# PMIC_Debug.net
KiCad netlist of a schematic drawn in Altium Designer
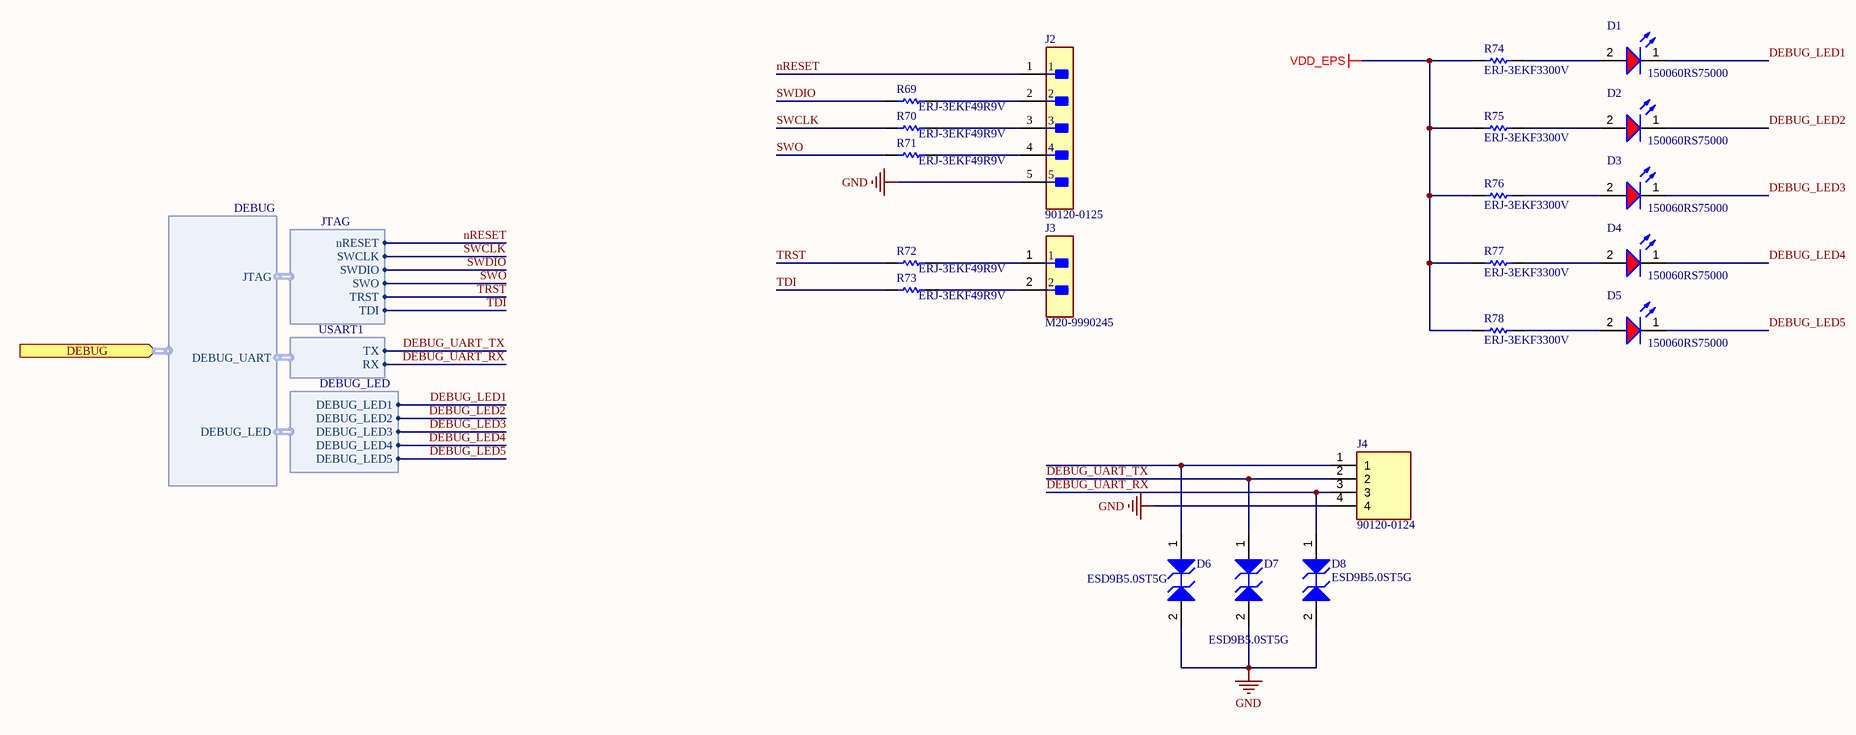
[diagram p0: PMIC_Debug.SchDoc]

(export (version "E")
  (design (tool "Eeschema 10.0.6"))
  (components
    (comp (ref "D1")
      (value "150060RS75000")
      (footprint "WL-SMCW_0603_150060xx75000")
      (description "LED Low-Power Uni-Color Red 630nm 2V 2-Pin Chip 0603(1608Metric) T/R")
      (libsource (lib "Altium Content Vault") (part "LED_Red_2A-1K"))
    )
    (comp (ref "D2")
      (value "150060RS75000")
      (footprint "WL-SMCW_0603_150060xx75000")
      (description "LED Low-Power Uni-Color Red 630nm 2V 2-Pin Chip 0603(1608Metric) T/R")
      (libsource (lib "Altium Content Vault") (part "LED_Red_2A-1K"))
    )
    (comp (ref "D3")
      (value "150060RS75000")
      (footprint "WL-SMCW_0603_150060xx75000")
      (description "LED Low-Power Uni-Color Red 630nm 2V 2-Pin Chip 0603(1608Metric) T/R")
      (libsource (lib "Altium Content Vault") (part "LED_Red_2A-1K"))
    )
    (comp (ref "D4")
      (value "150060RS75000")
      (footprint "WL-SMCW_0603_150060xx75000")
      (description "LED Low-Power Uni-Color Red 630nm 2V 2-Pin Chip 0603(1608Metric) T/R")
      (libsource (lib "Altium Content Vault") (part "LED_Red_2A-1K"))
    )
    (comp (ref "D5")
      (value "150060RS75000")
      (footprint "WL-SMCW_0603_150060xx75000")
      (description "LED Low-Power Uni-Color Red 630nm 2V 2-Pin Chip 0603(1608Metric) T/R")
      (libsource (lib "Altium Content Vault") (part "LED_Red_2A-1K"))
    )
    (comp (ref "D6")
      (value "ESD9B5.0ST5G")
      (footprint "ONSC-SOD-923-2-514AB-01_V")
      (fields (field (name "MANUFACTURER") "On Semiconductor"))
      (libsource (lib "Altium Content Vault") (part "ONSC-A1A2-2"))
    )
    (comp (ref "D7")
      (value "ESD9B5.0ST5G")
      (footprint "ONSC-SOD-923-2-514AB-01_V")
      (fields (field (name "MANUFACTURER") "On Semiconductor"))
      (libsource (lib "Altium Content Vault") (part "ONSC-A1A2-2"))
    )
    (comp (ref "D8")
      (value "ESD9B5.0ST5G")
      (footprint "ONSC-SOD-923-2-514AB-01_V")
      (fields (field (name "MANUFACTURER") "On Semiconductor"))
      (libsource (lib "Altium Content Vault") (part "ONSC-A1A2-2"))
    )
    (comp (ref "J2")
      (value "90120-0125")
      (footprint "FP-90120-0125-MFG")
      (description "90120-0125 2.54mm Pitch C-Grid III Header, Single Row, Vertical, 5 Circuits, Tin (Sn) Plating")
      (libsource (lib "Altium Content Vault") (part "bf93c07fd2649a848d0ec8585582aab"))
    )
    (comp (ref "J3")
      (value "M20-9990245")
      (footprint "FP-M20-9990245-MFG")
      (description "CONN HEADER VERT 2POS 2.54MM")
      (fields (field (name "VOLTAGE") "50V"))
      (libsource (lib "Altium Content Vault") (part "3bc925449376181038e59eaffc5286c"))
    )
    (comp (ref "J4")
      (value "90120-0124")
      (footprint "SamacSys:HDRV4W65P0X254_1X4_1016X254X945P")
      (description "Connector")
      (fields (field (name "MOUSER PART NUMBER") "538-90120-0124"))
      (libsource (lib "*") (part "90120-0124"))
    )
    (comp (ref "R69")
      (value "ERJ-3EKF49R9V")
      (footprint "RESC1608X55X30ML15T15")
      (fields (field (name "MANUFACTURER") "Panasonic"))
      (libsource (lib "Altium Content Vault") (part "RES"))
    )
    (comp (ref "R70")
      (value "ERJ-3EKF49R9V")
      (footprint "RESC1608X55X30ML15T15")
      (fields (field (name "MANUFACTURER") "Panasonic"))
      (libsource (lib "Altium Content Vault") (part "RES"))
    )
    (comp (ref "R71")
      (value "ERJ-3EKF49R9V")
      (footprint "RESC1608X55X30ML15T15")
      (fields (field (name "MANUFACTURER") "Panasonic"))
      (libsource (lib "Altium Content Vault") (part "RES"))
    )
    (comp (ref "R72")
      (value "ERJ-3EKF49R9V")
      (footprint "RESC1608X55X30ML15T15")
      (fields (field (name "MANUFACTURER") "Panasonic"))
      (libsource (lib "Altium Content Vault") (part "RES"))
    )
    (comp (ref "R73")
      (value "ERJ-3EKF49R9V")
      (footprint "RESC1608X55X30ML15T15")
      (fields (field (name "MANUFACTURER") "Panasonic"))
      (libsource (lib "Altium Content Vault") (part "RES"))
    )
    (comp (ref "R74")
      (value "ERJ-3EKF3300V")
      (footprint "RESC1608X55X30LL15T15")
      (description "Chip Resistor, 330 Ohm, +/- 1%, 0.1 W, -55 to 155 degC, 0603 (1608 Metric), RoHS, Tape and Reel")
      (libsource (lib "Altium Content Vault") (part "RES-2"))
    )
    (comp (ref "R75")
      (value "ERJ-3EKF3300V")
      (footprint "RESC1608X55X30LL15T15")
      (description "Chip Resistor, 330 Ohm, +/- 1%, 0.1 W, -55 to 155 degC, 0603 (1608 Metric), RoHS, Tape and Reel")
      (libsource (lib "Altium Content Vault") (part "RES-2"))
    )
    (comp (ref "R76")
      (value "ERJ-3EKF3300V")
      (footprint "RESC1608X55X30LL15T15")
      (description "Chip Resistor, 330 Ohm, +/- 1%, 0.1 W, -55 to 155 degC, 0603 (1608 Metric), RoHS, Tape and Reel")
      (libsource (lib "Altium Content Vault") (part "RES-2"))
    )
    (comp (ref "R77")
      (value "ERJ-3EKF3300V")
      (footprint "RESC1608X55X30LL15T15")
      (description "Chip Resistor, 330 Ohm, +/- 1%, 0.1 W, -55 to 155 degC, 0603 (1608 Metric), RoHS, Tape and Reel")
      (libsource (lib "Altium Content Vault") (part "RES-2"))
    )
    (comp (ref "R78")
      (value "ERJ-3EKF3300V")
      (footprint "RESC1608X55X30LL15T15")
      (description "Chip Resistor, 330 Ohm, +/- 1%, 0.1 W, -55 to 155 degC, 0603 (1608 Metric), RoHS, Tape and Reel")
      (libsource (lib "Altium Content Vault") (part "RES-2"))
    )
  )
  (nets
    (net (code "5") (name "/DEBUG_LED1") (class "Default")
      (node (ref "D1") (pin "1") (pinfunction "K_1") (pintype "passive"))
    )
    (net (code "6") (name "/DEBUG_LED2") (class "Default")
      (node (ref "D2") (pin "1") (pinfunction "K_1") (pintype "passive"))
    )
    (net (code "7") (name "/DEBUG_LED3") (class "Default")
      (node (ref "D3") (pin "1") (pinfunction "K_1") (pintype "passive"))
    )
    (net (code "8") (name "/DEBUG_LED4") (class "Default")
      (node (ref "D4") (pin "1") (pinfunction "K_1") (pintype "passive"))
    )
    (net (code "9") (name "/DEBUG_LED5") (class "Default")
      (node (ref "D5") (pin "1") (pinfunction "K_1") (pintype "passive"))
    )
    (net (code "10") (name "/DEBUG_UART_RX") (class "Default")
      (node (ref "D8") (pin "1") (pinfunction "A1_1") (pintype "passive"))
      (node (ref "J4") (pin "3") (pinfunction "3_3") (pintype "passive"))
    )
    (net (code "11") (name "/DEBUG_UART_TX") (class "Default")
      (node (ref "D7") (pin "1") (pinfunction "A1_1") (pintype "passive"))
      (node (ref "J4") (pin "2") (pinfunction "2_2") (pintype "passive"))
    )
    (net (code "12") (name "/SWCLK") (class "Default")
      (node (ref "R70") (pin "1") (pinfunction "1_1") (pintype "passive"))
    )
    (net (code "13") (name "/SWDIO") (class "Default")
      (node (ref "R69") (pin "1") (pinfunction "1_1") (pintype "passive"))
    )
    (net (code "14") (name "/SWO") (class "Default")
      (node (ref "R71") (pin "1") (pinfunction "1_1") (pintype "passive"))
    )
    (net (code "15") (name "/TDI") (class "Default")
      (node (ref "R73") (pin "1") (pinfunction "1_1") (pintype "passive"))
    )
    (net (code "16") (name "/TRST") (class "Default")
      (node (ref "R72") (pin "1") (pinfunction "1_1") (pintype "passive"))
    )
    (net (code "17") (name "/nRESET") (class "Default")
      (node (ref "J2") (pin "1") (pinfunction "1_1") (pintype "passive"))
    )
    (net (code "22") (name "GND") (class "Default")
      (node (ref "D6") (pin "2") (pinfunction "A2_2") (pintype "passive"))
      (node (ref "D7") (pin "2") (pinfunction "A2_2") (pintype "passive"))
      (node (ref "D8") (pin "2") (pinfunction "A2_2") (pintype "passive"))
      (node (ref "J2") (pin "5") (pinfunction "5_5") (pintype "passive"))
      (node (ref "J4") (pin "4") (pinfunction "4_4") (pintype "passive"))
    )
    (net (code "23") (name "Net-(D1-A)") (class "Default")
      (node (ref "D1") (pin "2") (pinfunction "A_2") (pintype "passive"))
      (node (ref "R74") (pin "2") (pinfunction "2_2") (pintype "passive"))
    )
    (net (code "24") (name "Net-(D2-A)") (class "Default")
      (node (ref "D2") (pin "2") (pinfunction "A_2") (pintype "passive"))
      (node (ref "R75") (pin "2") (pinfunction "2_2") (pintype "passive"))
    )
    (net (code "25") (name "Net-(D3-A)") (class "Default")
      (node (ref "D3") (pin "2") (pinfunction "A_2") (pintype "passive"))
      (node (ref "R76") (pin "2") (pinfunction "2_2") (pintype "passive"))
    )
    (net (code "26") (name "Net-(D4-A)") (class "Default")
      (node (ref "D4") (pin "2") (pinfunction "A_2") (pintype "passive"))
      (node (ref "R77") (pin "2") (pinfunction "2_2") (pintype "passive"))
    )
    (net (code "27") (name "Net-(D5-A)") (class "Default")
      (node (ref "D5") (pin "2") (pinfunction "A_2") (pintype "passive"))
      (node (ref "R78") (pin "2") (pinfunction "2_2") (pintype "passive"))
    )
    (net (code "28") (name "Net-(D6-A1)") (class "Default")
      (node (ref "D6") (pin "1") (pinfunction "A1_1") (pintype "passive"))
      (node (ref "J4") (pin "1") (pinfunction "1_1") (pintype "passive"))
    )
    (net (code "29") (name "Net-(J2-Pad2)") (class "Default")
      (node (ref "J2") (pin "2") (pinfunction "2_2") (pintype "passive"))
      (node (ref "R69") (pin "2") (pinfunction "2_2") (pintype "passive"))
    )
    (net (code "30") (name "Net-(J2-Pad3)") (class "Default")
      (node (ref "J2") (pin "3") (pinfunction "3_3") (pintype "passive"))
      (node (ref "R70") (pin "2") (pinfunction "2_2") (pintype "passive"))
    )
    (net (code "31") (name "Net-(J2-Pad4)") (class "Default")
      (node (ref "J2") (pin "4") (pinfunction "4_4") (pintype "passive"))
      (node (ref "R71") (pin "2") (pinfunction "2_2") (pintype "passive"))
    )
    (net (code "32") (name "Net-(J3-Pad1)") (class "Default")
      (node (ref "J3") (pin "1") (pinfunction "1_1") (pintype "passive"))
      (node (ref "R72") (pin "2") (pinfunction "2_2") (pintype "passive"))
    )
    (net (code "33") (name "Net-(J3-Pad2)") (class "Default")
      (node (ref "J3") (pin "2") (pinfunction "2_2") (pintype "passive"))
      (node (ref "R73") (pin "2") (pinfunction "2_2") (pintype "passive"))
    )
    (net (code "34") (name "VDD_EPS") (class "Default")
      (node (ref "R74") (pin "1") (pinfunction "1_1") (pintype "passive"))
      (node (ref "R75") (pin "1") (pinfunction "1_1") (pintype "passive"))
      (node (ref "R76") (pin "1") (pinfunction "1_1") (pintype "passive"))
      (node (ref "R77") (pin "1") (pinfunction "1_1") (pintype "passive"))
      (node (ref "R78") (pin "1") (pinfunction "1_1") (pintype "passive"))
    )
  )
)
